# Backlight_V2.net
KiCad netlist of a schematic drawn in Altium Designer
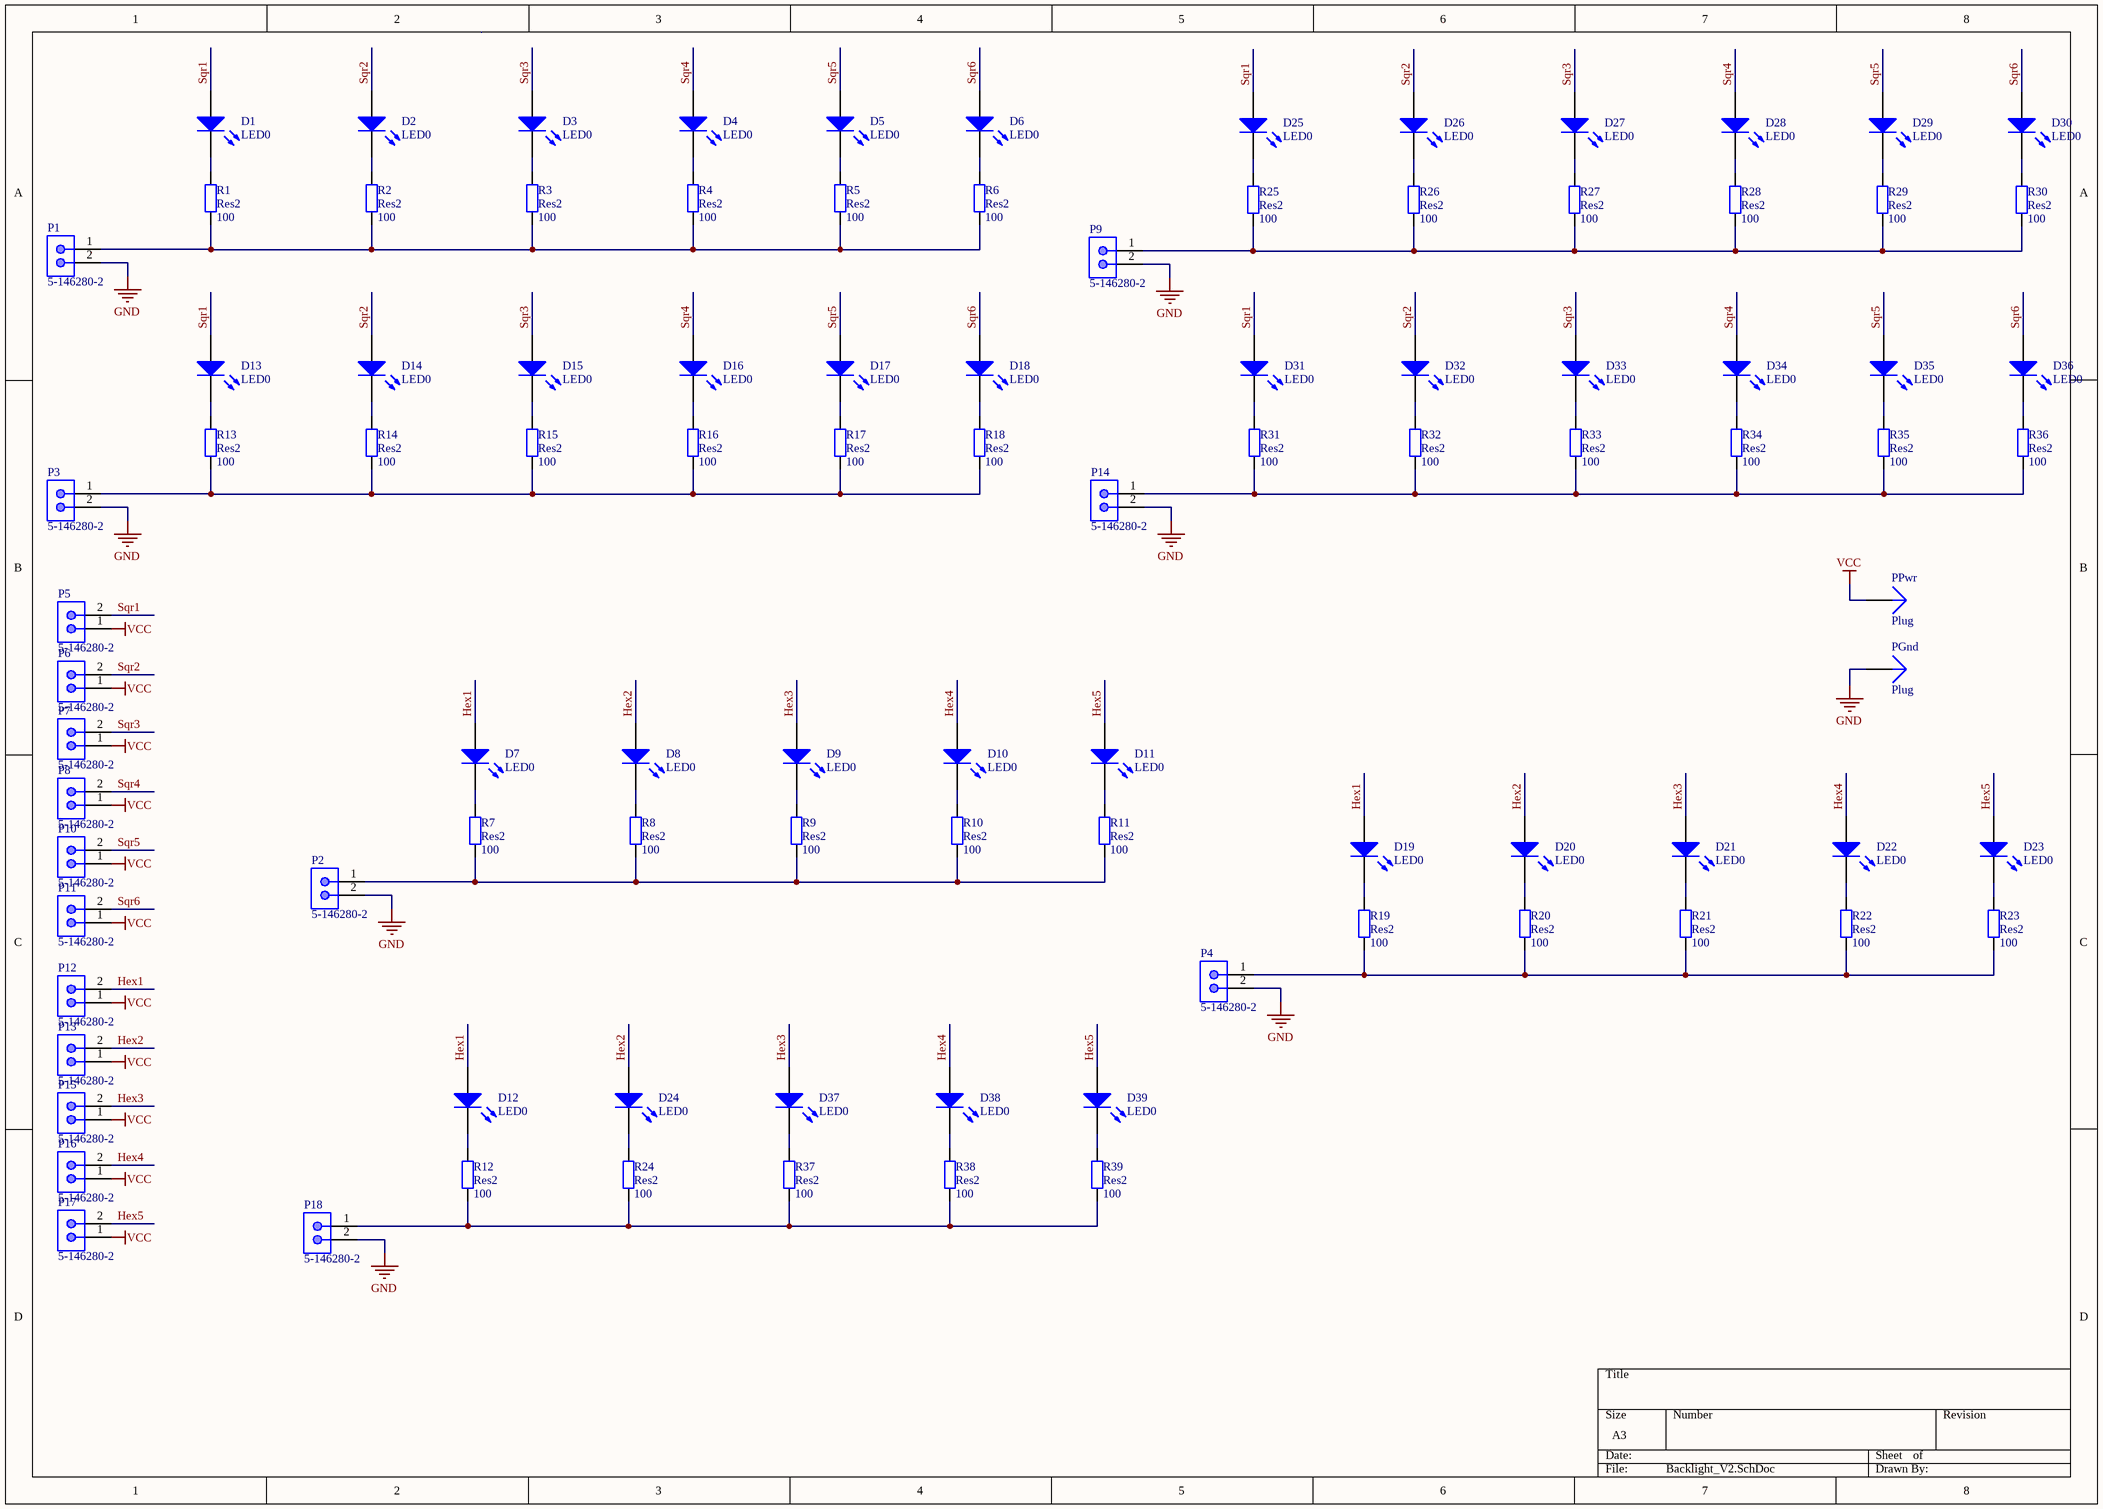
[diagram p0: Backlight_V2.SchDoc]

(export (version "E")
  (design (tool "Eeschema 10.0.6"))
  (components
    (comp (ref "D1")
      (value "LED0")
      (footprint "DIOM3528X07N")
      (description "Typical INFRARED GaAs LED")
      (fields (field (name "PUBLISHER") "Altium Limited"))
      (libsource (lib "Miscellaneous Devices") (part "LED0"))
    )
    (comp (ref "D2")
      (value "LED0")
      (footprint "DIOM3528X07N")
      (description "Typical INFRARED GaAs LED")
      (fields (field (name "PUBLISHER") "Altium Limited"))
      (libsource (lib "Miscellaneous Devices") (part "LED0"))
    )
    (comp (ref "D3")
      (value "LED0")
      (footprint "DIOM3528X07N")
      (description "Typical INFRARED GaAs LED")
      (fields (field (name "PUBLISHER") "Altium Limited"))
      (libsource (lib "Miscellaneous Devices") (part "LED0"))
    )
    (comp (ref "D4")
      (value "LED0")
      (footprint "DIOM3528X07N")
      (description "Typical INFRARED GaAs LED")
      (fields (field (name "PUBLISHER") "Altium Limited"))
      (libsource (lib "Miscellaneous Devices") (part "LED0"))
    )
    (comp (ref "D5")
      (value "LED0")
      (footprint "DIOM3528X07N")
      (description "Typical INFRARED GaAs LED")
      (fields (field (name "PUBLISHER") "Altium Limited"))
      (libsource (lib "Miscellaneous Devices") (part "LED0"))
    )
    (comp (ref "D6")
      (value "LED0")
      (footprint "DIOM3528X07N")
      (description "Typical INFRARED GaAs LED")
      (fields (field (name "PUBLISHER") "Altium Limited"))
      (libsource (lib "Miscellaneous Devices") (part "LED0"))
    )
    (comp (ref "D7")
      (value "LED0")
      (footprint "DIOM3528X07N")
      (description "Typical INFRARED GaAs LED")
      (fields (field (name "PUBLISHER") "Altium Limited"))
      (libsource (lib "Miscellaneous Devices") (part "LED0"))
    )
    (comp (ref "D8")
      (value "LED0")
      (footprint "DIOM3528X07N")
      (description "Typical INFRARED GaAs LED")
      (fields (field (name "PUBLISHER") "Altium Limited"))
      (libsource (lib "Miscellaneous Devices") (part "LED0"))
    )
    (comp (ref "D9")
      (value "LED0")
      (footprint "DIOM3528X07N")
      (description "Typical INFRARED GaAs LED")
      (fields (field (name "PUBLISHER") "Altium Limited"))
      (libsource (lib "Miscellaneous Devices") (part "LED0"))
    )
    (comp (ref "D10")
      (value "LED0")
      (footprint "DIOM3528X07N")
      (description "Typical INFRARED GaAs LED")
      (fields (field (name "PUBLISHER") "Altium Limited"))
      (libsource (lib "Miscellaneous Devices") (part "LED0"))
    )
    (comp (ref "D11")
      (value "LED0")
      (footprint "DIOM3528X07N")
      (description "Typical INFRARED GaAs LED")
      (fields (field (name "PUBLISHER") "Altium Limited"))
      (libsource (lib "Miscellaneous Devices") (part "LED0"))
    )
    (comp (ref "D12")
      (value "LED0")
      (footprint "DIOM3528X07N")
      (description "Typical INFRARED GaAs LED")
      (fields (field (name "PUBLISHER") "Altium Limited"))
      (libsource (lib "Miscellaneous Devices") (part "LED0"))
    )
    (comp (ref "D13")
      (value "LED0")
      (footprint "DIOM3528X07N")
      (description "Typical INFRARED GaAs LED")
      (fields (field (name "PUBLISHER") "Altium Limited"))
      (libsource (lib "Miscellaneous Devices") (part "LED0"))
    )
    (comp (ref "D14")
      (value "LED0")
      (footprint "DIOM3528X07N")
      (description "Typical INFRARED GaAs LED")
      (fields (field (name "PUBLISHER") "Altium Limited"))
      (libsource (lib "Miscellaneous Devices") (part "LED0"))
    )
    (comp (ref "D15")
      (value "LED0")
      (footprint "DIOM3528X07N")
      (description "Typical INFRARED GaAs LED")
      (fields (field (name "PUBLISHER") "Altium Limited"))
      (libsource (lib "Miscellaneous Devices") (part "LED0"))
    )
    (comp (ref "D16")
      (value "LED0")
      (footprint "DIOM3528X07N")
      (description "Typical INFRARED GaAs LED")
      (fields (field (name "PUBLISHER") "Altium Limited"))
      (libsource (lib "Miscellaneous Devices") (part "LED0"))
    )
    (comp (ref "D17")
      (value "LED0")
      (footprint "DIOM3528X07N")
      (description "Typical INFRARED GaAs LED")
      (fields (field (name "PUBLISHER") "Altium Limited"))
      (libsource (lib "Miscellaneous Devices") (part "LED0"))
    )
    (comp (ref "D18")
      (value "LED0")
      (footprint "DIOM3528X07N")
      (description "Typical INFRARED GaAs LED")
      (fields (field (name "PUBLISHER") "Altium Limited"))
      (libsource (lib "Miscellaneous Devices") (part "LED0"))
    )
    (comp (ref "D19")
      (value "LED0")
      (footprint "DIOM3528X07N")
      (description "Typical INFRARED GaAs LED")
      (fields (field (name "PUBLISHER") "Altium Limited"))
      (libsource (lib "Miscellaneous Devices") (part "LED0"))
    )
    (comp (ref "D20")
      (value "LED0")
      (footprint "DIOM3528X07N")
      (description "Typical INFRARED GaAs LED")
      (fields (field (name "PUBLISHER") "Altium Limited"))
      (libsource (lib "Miscellaneous Devices") (part "LED0"))
    )
    (comp (ref "D21")
      (value "LED0")
      (footprint "DIOM3528X07N")
      (description "Typical INFRARED GaAs LED")
      (fields (field (name "PUBLISHER") "Altium Limited"))
      (libsource (lib "Miscellaneous Devices") (part "LED0"))
    )
    (comp (ref "D22")
      (value "LED0")
      (footprint "DIOM3528X07N")
      (description "Typical INFRARED GaAs LED")
      (fields (field (name "PUBLISHER") "Altium Limited"))
      (libsource (lib "Miscellaneous Devices") (part "LED0"))
    )
    (comp (ref "D23")
      (value "LED0")
      (footprint "DIOM3528X07N")
      (description "Typical INFRARED GaAs LED")
      (fields (field (name "PUBLISHER") "Altium Limited"))
      (libsource (lib "Miscellaneous Devices") (part "LED0"))
    )
    (comp (ref "D24")
      (value "LED0")
      (footprint "DIOM3528X07N")
      (description "Typical INFRARED GaAs LED")
      (fields (field (name "PUBLISHER") "Altium Limited"))
      (libsource (lib "Miscellaneous Devices") (part "LED0"))
    )
    (comp (ref "D25")
      (value "LED0")
      (footprint "DIOM3528X07N")
      (description "Typical INFRARED GaAs LED")
      (fields (field (name "PUBLISHER") "Altium Limited"))
      (libsource (lib "Miscellaneous Devices") (part "LED0"))
    )
    (comp (ref "D26")
      (value "LED0")
      (footprint "DIOM3528X07N")
      (description "Typical INFRARED GaAs LED")
      (fields (field (name "PUBLISHER") "Altium Limited"))
      (libsource (lib "Miscellaneous Devices") (part "LED0"))
    )
    (comp (ref "D27")
      (value "LED0")
      (footprint "DIOM3528X07N")
      (description "Typical INFRARED GaAs LED")
      (fields (field (name "PUBLISHER") "Altium Limited"))
      (libsource (lib "Miscellaneous Devices") (part "LED0"))
    )
    (comp (ref "D28")
      (value "LED0")
      (footprint "DIOM3528X07N")
      (description "Typical INFRARED GaAs LED")
      (fields (field (name "PUBLISHER") "Altium Limited"))
      (libsource (lib "Miscellaneous Devices") (part "LED0"))
    )
    (comp (ref "D29")
      (value "LED0")
      (footprint "DIOM3528X07N")
      (description "Typical INFRARED GaAs LED")
      (fields (field (name "PUBLISHER") "Altium Limited"))
      (libsource (lib "Miscellaneous Devices") (part "LED0"))
    )
    (comp (ref "D30")
      (value "LED0")
      (footprint "DIOM3528X07N")
      (description "Typical INFRARED GaAs LED")
      (fields (field (name "PUBLISHER") "Altium Limited"))
      (libsource (lib "Miscellaneous Devices") (part "LED0"))
    )
    (comp (ref "D31")
      (value "LED0")
      (footprint "DIOM3528X07N")
      (description "Typical INFRARED GaAs LED")
      (fields (field (name "PUBLISHER") "Altium Limited"))
      (libsource (lib "Miscellaneous Devices") (part "LED0"))
    )
    (comp (ref "D32")
      (value "LED0")
      (footprint "DIOM3528X07N")
      (description "Typical INFRARED GaAs LED")
      (fields (field (name "PUBLISHER") "Altium Limited"))
      (libsource (lib "Miscellaneous Devices") (part "LED0"))
    )
    (comp (ref "D33")
      (value "LED0")
      (footprint "DIOM3528X07N")
      (description "Typical INFRARED GaAs LED")
      (fields (field (name "PUBLISHER") "Altium Limited"))
      (libsource (lib "Miscellaneous Devices") (part "LED0"))
    )
    (comp (ref "D34")
      (value "LED0")
      (footprint "DIOM3528X07N")
      (description "Typical INFRARED GaAs LED")
      (fields (field (name "PUBLISHER") "Altium Limited"))
      (libsource (lib "Miscellaneous Devices") (part "LED0"))
    )
    (comp (ref "D35")
      (value "LED0")
      (footprint "DIOM3528X07N")
      (description "Typical INFRARED GaAs LED")
      (fields (field (name "PUBLISHER") "Altium Limited"))
      (libsource (lib "Miscellaneous Devices") (part "LED0"))
    )
    (comp (ref "D36")
      (value "LED0")
      (footprint "DIOM3528X07N")
      (description "Typical INFRARED GaAs LED")
      (fields (field (name "PUBLISHER") "Altium Limited"))
      (libsource (lib "Miscellaneous Devices") (part "LED0"))
    )
    (comp (ref "D37")
      (value "LED0")
      (footprint "DIOM3528X07N")
      (description "Typical INFRARED GaAs LED")
      (fields (field (name "PUBLISHER") "Altium Limited"))
      (libsource (lib "Miscellaneous Devices") (part "LED0"))
    )
    (comp (ref "D38")
      (value "LED0")
      (footprint "DIOM3528X07N")
      (description "Typical INFRARED GaAs LED")
      (fields (field (name "PUBLISHER") "Altium Limited"))
      (libsource (lib "Miscellaneous Devices") (part "LED0"))
    )
    (comp (ref "D39")
      (value "LED0")
      (footprint "DIOM3528X07N")
      (description "Typical INFRARED GaAs LED")
      (fields (field (name "PUBLISHER") "Altium Limited"))
      (libsource (lib "Miscellaneous Devices") (part "LED0"))
    )
    (comp (ref "P1")
      (value "5-146280-2")
      (footprint "TECO-5-146280-2_V")
      (fields (field (name "MANUFACTURER") "TE Connectivity"))
      (libsource (lib "") (part "CN-1P-M-R2_1"))
    )
    (comp (ref "P2")
      (value "5-146280-2")
      (footprint "TECO-5-146280-2_V")
      (fields (field (name "MANUFACTURER") "TE Connectivity"))
      (libsource (lib "") (part "CN-1P-M-R2_1"))
    )
    (comp (ref "P3")
      (value "5-146280-2")
      (footprint "TECO-5-146280-2_V")
      (fields (field (name "MANUFACTURER") "TE Connectivity"))
      (libsource (lib "") (part "CN-1P-M-R2_1"))
    )
    (comp (ref "P4")
      (value "5-146280-2")
      (footprint "TECO-5-146280-2_V")
      (fields (field (name "MANUFACTURER") "TE Connectivity"))
      (libsource (lib "") (part "CN-1P-M-R2_1"))
    )
    (comp (ref "P5")
      (value "5-146280-2")
      (footprint "TECO-5-146280-2_V")
      (fields (field (name "MANUFACTURER") "TE Connectivity"))
      (libsource (lib "Altium Content Vault") (part "CN-1P-M-R2"))
    )
    (comp (ref "P6")
      (value "5-146280-2")
      (footprint "TECO-5-146280-2_V")
      (fields (field (name "MANUFACTURER") "TE Connectivity"))
      (libsource (lib "Altium Content Vault") (part "CN-1P-M-R2"))
    )
    (comp (ref "P7")
      (value "5-146280-2")
      (footprint "TECO-5-146280-2_V")
      (fields (field (name "MANUFACTURER") "TE Connectivity"))
      (libsource (lib "Altium Content Vault") (part "CN-1P-M-R2"))
    )
    (comp (ref "P8")
      (value "5-146280-2")
      (footprint "TECO-5-146280-2_V")
      (fields (field (name "MANUFACTURER") "TE Connectivity"))
      (libsource (lib "Altium Content Vault") (part "CN-1P-M-R2"))
    )
    (comp (ref "P9")
      (value "5-146280-2")
      (footprint "TECO-5-146280-2_V")
      (fields (field (name "MANUFACTURER") "TE Connectivity"))
      (libsource (lib "") (part "CN-1P-M-R2_1"))
    )
    (comp (ref "P10")
      (value "5-146280-2")
      (footprint "TECO-5-146280-2_V")
      (fields (field (name "MANUFACTURER") "TE Connectivity"))
      (libsource (lib "Altium Content Vault") (part "CN-1P-M-R2"))
    )
    (comp (ref "P11")
      (value "5-146280-2")
      (footprint "TECO-5-146280-2_V")
      (fields (field (name "MANUFACTURER") "TE Connectivity"))
      (libsource (lib "Altium Content Vault") (part "CN-1P-M-R2"))
    )
    (comp (ref "P12")
      (value "5-146280-2")
      (footprint "TECO-5-146280-2_V")
      (fields (field (name "MANUFACTURER") "TE Connectivity"))
      (libsource (lib "Altium Content Vault") (part "CN-1P-M-R2"))
    )
    (comp (ref "P13")
      (value "5-146280-2")
      (footprint "TECO-5-146280-2_V")
      (fields (field (name "MANUFACTURER") "TE Connectivity"))
      (libsource (lib "Altium Content Vault") (part "CN-1P-M-R2"))
    )
    (comp (ref "P14")
      (value "5-146280-2")
      (footprint "TECO-5-146280-2_V")
      (fields (field (name "MANUFACTURER") "TE Connectivity"))
      (libsource (lib "") (part "CN-1P-M-R2_1"))
    )
    (comp (ref "P15")
      (value "5-146280-2")
      (footprint "TECO-5-146280-2_V")
      (fields (field (name "MANUFACTURER") "TE Connectivity"))
      (libsource (lib "Altium Content Vault") (part "CN-1P-M-R2"))
    )
    (comp (ref "P16")
      (value "5-146280-2")
      (footprint "TECO-5-146280-2_V")
      (fields (field (name "MANUFACTURER") "TE Connectivity"))
      (libsource (lib "Altium Content Vault") (part "CN-1P-M-R2"))
    )
    (comp (ref "P17")
      (value "5-146280-2")
      (footprint "TECO-5-146280-2_V")
      (fields (field (name "MANUFACTURER") "TE Connectivity"))
      (libsource (lib "Altium Content Vault") (part "CN-1P-M-R2"))
    )
    (comp (ref "P18")
      (value "5-146280-2")
      (footprint "TECO-5-146280-2_V")
      (fields (field (name "MANUFACTURER") "TE Connectivity"))
      (libsource (lib "") (part "CN-1P-M-R2_1"))
    )
    (comp (ref "PGnd")
      (value "Plug")
      (footprint "Bananenbuchse")
      (fields (field (name "PUBLISHER") "Altium Limited"))
      (libsource (lib "Miscellaneous Connectors") (part "Plug"))
    )
    (comp (ref "PPwr")
      (value "Plug")
      (footprint "Bananenbuchse")
      (fields (field (name "PUBLISHER") "Altium Limited"))
      (libsource (lib "Miscellaneous Connectors") (part "Plug"))
    )
    (comp (ref "R1")
      (value "Res2")
      (footprint "6-0805_N")
      (description "Resistor")
      (fields (field (name "ALTIUM_VALUE") "100") (field (name "PUBLISHER") "Altium Limited"))
      (libsource (lib "Miscellaneous Devices") (part "Res2"))
    )
    (comp (ref "R2")
      (value "Res2")
      (footprint "6-0805_N")
      (description "Resistor")
      (fields (field (name "ALTIUM_VALUE") "100") (field (name "PUBLISHER") "Altium Limited"))
      (libsource (lib "Miscellaneous Devices") (part "Res2"))
    )
    (comp (ref "R3")
      (value "Res2")
      (footprint "6-0805_N")
      (description "Resistor")
      (fields (field (name "ALTIUM_VALUE") "100") (field (name "PUBLISHER") "Altium Limited"))
      (libsource (lib "Miscellaneous Devices") (part "Res2"))
    )
    (comp (ref "R4")
      (value "Res2")
      (footprint "6-0805_N")
      (description "Resistor")
      (fields (field (name "ALTIUM_VALUE") "100") (field (name "PUBLISHER") "Altium Limited"))
      (libsource (lib "Miscellaneous Devices") (part "Res2"))
    )
    (comp (ref "R5")
      (value "Res2")
      (footprint "6-0805_N")
      (description "Resistor")
      (fields (field (name "ALTIUM_VALUE") "100") (field (name "PUBLISHER") "Altium Limited"))
      (libsource (lib "Miscellaneous Devices") (part "Res2"))
    )
    (comp (ref "R6")
      (value "Res2")
      (footprint "6-0805_N")
      (description "Resistor")
      (fields (field (name "ALTIUM_VALUE") "100") (field (name "PUBLISHER") "Altium Limited"))
      (libsource (lib "Miscellaneous Devices") (part "Res2"))
    )
    (comp (ref "R7")
      (value "Res2")
      (footprint "6-0805_N")
      (description "Resistor")
      (fields (field (name "ALTIUM_VALUE") "100") (field (name "PUBLISHER") "Altium Limited"))
      (libsource (lib "Miscellaneous Devices") (part "Res2"))
    )
    (comp (ref "R8")
      (value "Res2")
      (footprint "6-0805_N")
      (description "Resistor")
      (fields (field (name "ALTIUM_VALUE") "100") (field (name "PUBLISHER") "Altium Limited"))
      (libsource (lib "Miscellaneous Devices") (part "Res2"))
    )
    (comp (ref "R9")
      (value "Res2")
      (footprint "6-0805_N")
      (description "Resistor")
      (fields (field (name "ALTIUM_VALUE") "100") (field (name "PUBLISHER") "Altium Limited"))
      (libsource (lib "Miscellaneous Devices") (part "Res2"))
    )
    (comp (ref "R10")
      (value "Res2")
      (footprint "6-0805_N")
      (description "Resistor")
      (fields (field (name "ALTIUM_VALUE") "100") (field (name "PUBLISHER") "Altium Limited"))
      (libsource (lib "Miscellaneous Devices") (part "Res2"))
    )
    (comp (ref "R11")
      (value "Res2")
      (footprint "6-0805_N")
      (description "Resistor")
      (fields (field (name "ALTIUM_VALUE") "100") (field (name "PUBLISHER") "Altium Limited"))
      (libsource (lib "Miscellaneous Devices") (part "Res2"))
    )
    (comp (ref "R12")
      (value "Res2")
      (footprint "6-0805_N")
      (description "Resistor")
      (fields (field (name "ALTIUM_VALUE") "100") (field (name "PUBLISHER") "Altium Limited"))
      (libsource (lib "Miscellaneous Devices") (part "Res2"))
    )
    (comp (ref "R13")
      (value "Res2")
      (footprint "6-0805_N")
      (description "Resistor")
      (fields (field (name "ALTIUM_VALUE") "100") (field (name "PUBLISHER") "Altium Limited"))
      (libsource (lib "Miscellaneous Devices") (part "Res2"))
    )
    (comp (ref "R14")
      (value "Res2")
      (footprint "6-0805_N")
      (description "Resistor")
      (fields (field (name "ALTIUM_VALUE") "100") (field (name "PUBLISHER") "Altium Limited"))
      (libsource (lib "Miscellaneous Devices") (part "Res2"))
    )
    (comp (ref "R15")
      (value "Res2")
      (footprint "6-0805_N")
      (description "Resistor")
      (fields (field (name "ALTIUM_VALUE") "100") (field (name "PUBLISHER") "Altium Limited"))
      (libsource (lib "Miscellaneous Devices") (part "Res2"))
    )
    (comp (ref "R16")
      (value "Res2")
      (footprint "6-0805_N")
      (description "Resistor")
      (fields (field (name "ALTIUM_VALUE") "100") (field (name "PUBLISHER") "Altium Limited"))
      (libsource (lib "Miscellaneous Devices") (part "Res2"))
    )
    (comp (ref "R17")
      (value "Res2")
      (footprint "6-0805_N")
      (description "Resistor")
      (fields (field (name "ALTIUM_VALUE") "100") (field (name "PUBLISHER") "Altium Limited"))
      (libsource (lib "Miscellaneous Devices") (part "Res2"))
    )
    (comp (ref "R18")
      (value "Res2")
      (footprint "6-0805_N")
      (description "Resistor")
      (fields (field (name "ALTIUM_VALUE") "100") (field (name "PUBLISHER") "Altium Limited"))
      (libsource (lib "Miscellaneous Devices") (part "Res2"))
    )
    (comp (ref "R19")
      (value "Res2")
      (footprint "6-0805_N")
      (description "Resistor")
      (fields (field (name "ALTIUM_VALUE") "100") (field (name "PUBLISHER") "Altium Limited"))
      (libsource (lib "Miscellaneous Devices") (part "Res2"))
    )
    (comp (ref "R20")
      (value "Res2")
      (footprint "6-0805_N")
      (description "Resistor")
      (fields (field (name "ALTIUM_VALUE") "100") (field (name "PUBLISHER") "Altium Limited"))
      (libsource (lib "Miscellaneous Devices") (part "Res2"))
    )
    (comp (ref "R21")
      (value "Res2")
      (footprint "6-0805_N")
      (description "Resistor")
      (fields (field (name "ALTIUM_VALUE") "100") (field (name "PUBLISHER") "Altium Limited"))
      (libsource (lib "Miscellaneous Devices") (part "Res2"))
    )
    (comp (ref "R22")
      (value "Res2")
      (footprint "6-0805_N")
      (description "Resistor")
      (fields (field (name "ALTIUM_VALUE") "100") (field (name "PUBLISHER") "Altium Limited"))
      (libsource (lib "Miscellaneous Devices") (part "Res2"))
    )
    (comp (ref "R23")
      (value "Res2")
      (footprint "6-0805_N")
      (description "Resistor")
      (fields (field (name "ALTIUM_VALUE") "100") (field (name "PUBLISHER") "Altium Limited"))
      (libsource (lib "Miscellaneous Devices") (part "Res2"))
    )
    (comp (ref "R24")
      (value "Res2")
      (footprint "6-0805_N")
      (description "Resistor")
      (fields (field (name "ALTIUM_VALUE") "100") (field (name "PUBLISHER") "Altium Limited"))
      (libsource (lib "Miscellaneous Devices") (part "Res2"))
    )
    (comp (ref "R25")
      (value "Res2")
      (footprint "6-0805_N")
      (description "Resistor")
      (fields (field (name "ALTIUM_VALUE") "100") (field (name "PUBLISHER") "Altium Limited"))
      (libsource (lib "Miscellaneous Devices") (part "Res2"))
    )
    (comp (ref "R26")
      (value "Res2")
      (footprint "6-0805_N")
      (description "Resistor")
      (fields (field (name "ALTIUM_VALUE") "100") (field (name "PUBLISHER") "Altium Limited"))
      (libsource (lib "Miscellaneous Devices") (part "Res2"))
    )
    (comp (ref "R27")
      (value "Res2")
      (footprint "6-0805_N")
      (description "Resistor")
      (fields (field (name "ALTIUM_VALUE") "100") (field (name "PUBLISHER") "Altium Limited"))
      (libsource (lib "Miscellaneous Devices") (part "Res2"))
    )
    (comp (ref "R28")
      (value "Res2")
      (footprint "6-0805_N")
      (description "Resistor")
      (fields (field (name "ALTIUM_VALUE") "100") (field (name "PUBLISHER") "Altium Limited"))
      (libsource (lib "Miscellaneous Devices") (part "Res2"))
    )
    (comp (ref "R29")
      (value "Res2")
      (footprint "6-0805_N")
      (description "Resistor")
      (fields (field (name "ALTIUM_VALUE") "100") (field (name "PUBLISHER") "Altium Limited"))
      (libsource (lib "Miscellaneous Devices") (part "Res2"))
    )
    (comp (ref "R30")
      (value "Res2")
      (footprint "6-0805_N")
      (description "Resistor")
      (fields (field (name "ALTIUM_VALUE") "100") (field (name "PUBLISHER") "Altium Limited"))
      (libsource (lib "Miscellaneous Devices") (part "Res2"))
    )
    (comp (ref "R31")
      (value "Res2")
      (footprint "6-0805_N")
      (description "Resistor")
      (fields (field (name "ALTIUM_VALUE") "100") (field (name "PUBLISHER") "Altium Limited"))
      (libsource (lib "Miscellaneous Devices") (part "Res2"))
    )
    (comp (ref "R32")
      (value "Res2")
      (footprint "6-0805_N")
      (description "Resistor")
      (fields (field (name "ALTIUM_VALUE") "100") (field (name "PUBLISHER") "Altium Limited"))
      (libsource (lib "Miscellaneous Devices") (part "Res2"))
    )
    (comp (ref "R33")
      (value "Res2")
      (footprint "6-0805_N")
      (description "Resistor")
      (fields (field (name "ALTIUM_VALUE") "100") (field (name "PUBLISHER") "Altium Limited"))
      (libsource (lib "Miscellaneous Devices") (part "Res2"))
    )
    (comp (ref "R34")
      (value "Res2")
      (footprint "6-0805_N")
      (description "Resistor")
      (fields (field (name "ALTIUM_VALUE") "100") (field (name "PUBLISHER") "Altium Limited"))
      (libsource (lib "Miscellaneous Devices") (part "Res2"))
    )
    (comp (ref "R35")
      (value "Res2")
      (footprint "6-0805_N")
      (description "Resistor")
      (fields (field (name "ALTIUM_VALUE") "100") (field (name "PUBLISHER") "Altium Limited"))
      (libsource (lib "Miscellaneous Devices") (part "Res2"))
    )
    (comp (ref "R36")
      (value "Res2")
      (footprint "6-0805_N")
      (description "Resistor")
      (fields (field (name "ALTIUM_VALUE") "100") (field (name "PUBLISHER") "Altium Limited"))
      (libsource (lib "Miscellaneous Devices") (part "Res2"))
    )
    (comp (ref "R37")
      (value "Res2")
      (footprint "6-0805_N")
      (description "Resistor")
      (fields (field (name "ALTIUM_VALUE") "100") (field (name "PUBLISHER") "Altium Limited"))
      (libsource (lib "Miscellaneous Devices") (part "Res2"))
    )
    (comp (ref "R38")
      (value "Res2")
      (footprint "6-0805_N")
      (description "Resistor")
      (fields (field (name "ALTIUM_VALUE") "100") (field (name "PUBLISHER") "Altium Limited"))
      (libsource (lib "Miscellaneous Devices") (part "Res2"))
    )
    (comp (ref "R39")
      (value "Res2")
      (footprint "6-0805_N")
      (description "Resistor")
      (fields (field (name "ALTIUM_VALUE") "100") (field (name "PUBLISHER") "Altium Limited"))
      (libsource (lib "Miscellaneous Devices") (part "Res2"))
    )
  )
  (nets
    (net (code "1") (name "/Hex1") (class "Default")
      (node (ref "D12") (pin "1") (pinfunction "A_1") (pintype "passive"))
      (node (ref "D19") (pin "1") (pinfunction "A_1") (pintype "passive"))
      (node (ref "D7") (pin "1") (pinfunction "A_1") (pintype "passive"))
      (node (ref "P12") (pin "2") (pinfunction "2_2") (pintype "passive"))
    )
    (net (code "2") (name "/Hex2") (class "Default")
      (node (ref "D20") (pin "1") (pinfunction "A_1") (pintype "passive"))
      (node (ref "D24") (pin "1") (pinfunction "A_1") (pintype "passive"))
      (node (ref "D8") (pin "1") (pinfunction "A_1") (pintype "passive"))
      (node (ref "P13") (pin "2") (pinfunction "2_2") (pintype "passive"))
    )
    (net (code "3") (name "/Hex3") (class "Default")
      (node (ref "D21") (pin "1") (pinfunction "A_1") (pintype "passive"))
      (node (ref "D37") (pin "1") (pinfunction "A_1") (pintype "passive"))
      (node (ref "D9") (pin "1") (pinfunction "A_1") (pintype "passive"))
      (node (ref "P15") (pin "2") (pinfunction "2_2") (pintype "passive"))
    )
    (net (code "4") (name "/Hex4") (class "Default")
      (node (ref "D10") (pin "1") (pinfunction "A_1") (pintype "passive"))
      (node (ref "D22") (pin "1") (pinfunction "A_1") (pintype "passive"))
      (node (ref "D38") (pin "1") (pinfunction "A_1") (pintype "passive"))
      (node (ref "P16") (pin "2") (pinfunction "2_2") (pintype "passive"))
    )
    (net (code "5") (name "/Hex5") (class "Default")
      (node (ref "D11") (pin "1") (pinfunction "A_1") (pintype "passive"))
      (node (ref "D23") (pin "1") (pinfunction "A_1") (pintype "passive"))
      (node (ref "D39") (pin "1") (pinfunction "A_1") (pintype "passive"))
      (node (ref "P17") (pin "2") (pinfunction "2_2") (pintype "passive"))
    )
    (net (code "6") (name "/Sqr1") (class "Default")
      (node (ref "D1") (pin "1") (pinfunction "A_1") (pintype "passive"))
      (node (ref "D13") (pin "1") (pinfunction "A_1") (pintype "passive"))
      (node (ref "D25") (pin "1") (pinfunction "A_1") (pintype "passive"))
      (node (ref "D31") (pin "1") (pinfunction "A_1") (pintype "passive"))
      (node (ref "P5") (pin "2") (pinfunction "2_2") (pintype "passive"))
    )
    (net (code "7") (name "/Sqr2") (class "Default")
      (node (ref "D14") (pin "1") (pinfunction "A_1") (pintype "passive"))
      (node (ref "D2") (pin "1") (pinfunction "A_1") (pintype "passive"))
      (node (ref "D26") (pin "1") (pinfunction "A_1") (pintype "passive"))
      (node (ref "D32") (pin "1") (pinfunction "A_1") (pintype "passive"))
      (node (ref "P6") (pin "2") (pinfunction "2_2") (pintype "passive"))
    )
    (net (code "8") (name "/Sqr3") (class "Default")
      (node (ref "D15") (pin "1") (pinfunction "A_1") (pintype "passive"))
      (node (ref "D27") (pin "1") (pinfunction "A_1") (pintype "passive"))
      (node (ref "D3") (pin "1") (pinfunction "A_1") (pintype "passive"))
      (node (ref "D33") (pin "1") (pinfunction "A_1") (pintype "passive"))
      (node (ref "P7") (pin "2") (pinfunction "2_2") (pintype "passive"))
    )
    (net (code "9") (name "/Sqr4") (class "Default")
      (node (ref "D16") (pin "1") (pinfunction "A_1") (pintype "passive"))
      (node (ref "D28") (pin "1") (pinfunction "A_1") (pintype "passive"))
      (node (ref "D34") (pin "1") (pinfunction "A_1") (pintype "passive"))
      (node (ref "D4") (pin "1") (pinfunction "A_1") (pintype "passive"))
      (node (ref "P8") (pin "2") (pinfunction "2_2") (pintype "passive"))
    )
    (net (code "10") (name "/Sqr5") (class "Default")
      (node (ref "D17") (pin "1") (pinfunction "A_1") (pintype "passive"))
      (node (ref "D29") (pin "1") (pinfunction "A_1") (pintype "passive"))
      (node (ref "D35") (pin "1") (pinfunction "A_1") (pintype "passive"))
      (node (ref "D5") (pin "1") (pinfunction "A_1") (pintype "passive"))
      (node (ref "P10") (pin "2") (pinfunction "2_2") (pintype "passive"))
    )
    (net (code "11") (name "/Sqr6") (class "Default")
      (node (ref "D18") (pin "1") (pinfunction "A_1") (pintype "passive"))
      (node (ref "D30") (pin "1") (pinfunction "A_1") (pintype "passive"))
      (node (ref "D36") (pin "1") (pinfunction "A_1") (pintype "passive"))
      (node (ref "D6") (pin "1") (pinfunction "A_1") (pintype "passive"))
      (node (ref "P11") (pin "2") (pinfunction "2_2") (pintype "passive"))
    )
    (net (code "12") (name "GND") (class "Default")
      (node (ref "P1") (pin "2") (pinfunction "2_2") (pintype "passive"))
      (node (ref "P14") (pin "2") (pinfunction "2_2") (pintype "passive"))
      (node (ref "P18") (pin "2") (pinfunction "2_2") (pintype "passive"))
      (node (ref "P2") (pin "2") (pinfunction "2_2") (pintype "passive"))
      (node (ref "P3") (pin "2") (pinfunction "2_2") (pintype "passive"))
      (node (ref "P4") (pin "2") (pinfunction "2_2") (pintype "passive"))
      (node (ref "P9") (pin "2") (pinfunction "2_2") (pintype "passive"))
      (node (ref "PGnd") (pin "1") (pinfunction "1_1") (pintype "passive"))
    )
    (net (code "13") (name "Net-(D1-K)") (class "Default")
      (node (ref "D1") (pin "2") (pinfunction "K_2") (pintype "passive"))
      (node (ref "R1") (pin "2") (pinfunction "2_2") (pintype "passive"))
    )
    (net (code "14") (name "Net-(D2-K)") (class "Default")
      (node (ref "D2") (pin "2") (pinfunction "K_2") (pintype "passive"))
      (node (ref "R2") (pin "2") (pinfunction "2_2") (pintype "passive"))
    )
    (net (code "15") (name "Net-(D3-K)") (class "Default")
      (node (ref "D3") (pin "2") (pinfunction "K_2") (pintype "passive"))
      (node (ref "R3") (pin "2") (pinfunction "2_2") (pintype "passive"))
    )
    (net (code "16") (name "Net-(D4-K)") (class "Default")
      (node (ref "D4") (pin "2") (pinfunction "K_2") (pintype "passive"))
      (node (ref "R4") (pin "2") (pinfunction "2_2") (pintype "passive"))
    )
    (net (code "17") (name "Net-(D5-K)") (class "Default")
      (node (ref "D5") (pin "2") (pinfunction "K_2") (pintype "passive"))
      (node (ref "R5") (pin "2") (pinfunction "2_2") (pintype "passive"))
    )
    (net (code "18") (name "Net-(D6-K)") (class "Default")
      (node (ref "D6") (pin "2") (pinfunction "K_2") (pintype "passive"))
      (node (ref "R6") (pin "2") (pinfunction "2_2") (pintype "passive"))
    )
    (net (code "19") (name "Net-(D7-K)") (class "Default")
      (node (ref "D7") (pin "2") (pinfunction "K_2") (pintype "passive"))
      (node (ref "R7") (pin "2") (pinfunction "2_2") (pintype "passive"))
    )
    (net (code "20") (name "Net-(D8-K)") (class "Default")
      (node (ref "D8") (pin "2") (pinfunction "K_2") (pintype "passive"))
      (node (ref "R8") (pin "2") (pinfunction "2_2") (pintype "passive"))
    )
    (net (code "21") (name "Net-(D9-K)") (class "Default")
      (node (ref "D9") (pin "2") (pinfunction "K_2") (pintype "passive"))
      (node (ref "R9") (pin "2") (pinfunction "2_2") (pintype "passive"))
    )
    (net (code "22") (name "Net-(D10-K)") (class "Default")
      (node (ref "D10") (pin "2") (pinfunction "K_2") (pintype "passive"))
      (node (ref "R10") (pin "2") (pinfunction "2_2") (pintype "passive"))
    )
    (net (code "23") (name "Net-(D11-K)") (class "Default")
      (node (ref "D11") (pin "2") (pinfunction "K_2") (pintype "passive"))
      (node (ref "R11") (pin "2") (pinfunction "2_2") (pintype "passive"))
    )
    (net (code "24") (name "Net-(D12-K)") (class "Default")
      (node (ref "D12") (pin "2") (pinfunction "K_2") (pintype "passive"))
      (node (ref "R12") (pin "2") (pinfunction "2_2") (pintype "passive"))
    )
    (net (code "25") (name "Net-(D13-K)") (class "Default")
      (node (ref "D13") (pin "2") (pinfunction "K_2") (pintype "passive"))
      (node (ref "R13") (pin "2") (pinfunction "2_2") (pintype "passive"))
    )
    (net (code "26") (name "Net-(D14-K)") (class "Default")
      (node (ref "D14") (pin "2") (pinfunction "K_2") (pintype "passive"))
      (node (ref "R14") (pin "2") (pinfunction "2_2") (pintype "passive"))
    )
    (net (code "27") (name "Net-(D15-K)") (class "Default")
      (node (ref "D15") (pin "2") (pinfunction "K_2") (pintype "passive"))
      (node (ref "R15") (pin "2") (pinfunction "2_2") (pintype "passive"))
    )
    (net (code "28") (name "Net-(D16-K)") (class "Default")
      (node (ref "D16") (pin "2") (pinfunction "K_2") (pintype "passive"))
      (node (ref "R16") (pin "2") (pinfunction "2_2") (pintype "passive"))
    )
    (net (code "29") (name "Net-(D17-K)") (class "Default")
      (node (ref "D17") (pin "2") (pinfunction "K_2") (pintype "passive"))
      (node (ref "R17") (pin "2") (pinfunction "2_2") (pintype "passive"))
    )
    (net (code "30") (name "Net-(D18-K)") (class "Default")
      (node (ref "D18") (pin "2") (pinfunction "K_2") (pintype "passive"))
      (node (ref "R18") (pin "2") (pinfunction "2_2") (pintype "passive"))
    )
    (net (code "31") (name "Net-(D19-K)") (class "Default")
      (node (ref "D19") (pin "2") (pinfunction "K_2") (pintype "passive"))
      (node (ref "R19") (pin "2") (pinfunction "2_2") (pintype "passive"))
    )
    (net (code "32") (name "Net-(D20-K)") (class "Default")
      (node (ref "D20") (pin "2") (pinfunction "K_2") (pintype "passive"))
      (node (ref "R20") (pin "2") (pinfunction "2_2") (pintype "passive"))
    )
    (net (code "33") (name "Net-(D21-K)") (class "Default")
      (node (ref "D21") (pin "2") (pinfunction "K_2") (pintype "passive"))
      (node (ref "R21") (pin "2") (pinfunction "2_2") (pintype "passive"))
    )
    (net (code "34") (name "Net-(D22-K)") (class "Default")
      (node (ref "D22") (pin "2") (pinfunction "K_2") (pintype "passive"))
      (node (ref "R22") (pin "2") (pinfunction "2_2") (pintype "passive"))
    )
    (net (code "35") (name "Net-(D23-K)") (class "Default")
      (node (ref "D23") (pin "2") (pinfunction "K_2") (pintype "passive"))
      (node (ref "R23") (pin "2") (pinfunction "2_2") (pintype "passive"))
    )
    (net (code "36") (name "Net-(D24-K)") (class "Default")
      (node (ref "D24") (pin "2") (pinfunction "K_2") (pintype "passive"))
      (node (ref "R24") (pin "2") (pinfunction "2_2") (pintype "passive"))
    )
    (net (code "37") (name "Net-(D25-K)") (class "Default")
      (node (ref "D25") (pin "2") (pinfunction "K_2") (pintype "passive"))
      (node (ref "R25") (pin "2") (pinfunction "2_2") (pintype "passive"))
    )
    (net (code "38") (name "Net-(D26-K)") (class "Default")
      (node (ref "D26") (pin "2") (pinfunction "K_2") (pintype "passive"))
      (node (ref "R26") (pin "2") (pinfunction "2_2") (pintype "passive"))
    )
    (net (code "39") (name "Net-(D27-K)") (class "Default")
      (node (ref "D27") (pin "2") (pinfunction "K_2") (pintype "passive"))
      (node (ref "R27") (pin "2") (pinfunction "2_2") (pintype "passive"))
    )
    (net (code "40") (name "Net-(D28-K)") (class "Default")
      (node (ref "D28") (pin "2") (pinfunction "K_2") (pintype "passive"))
      (node (ref "R28") (pin "2") (pinfunction "2_2") (pintype "passive"))
    )
    (net (code "41") (name "Net-(D29-K)") (class "Default")
      (node (ref "D29") (pin "2") (pinfunction "K_2") (pintype "passive"))
      (node (ref "R29") (pin "2") (pinfunction "2_2") (pintype "passive"))
    )
    (net (code "42") (name "Net-(D30-K)") (class "Default")
      (node (ref "D30") (pin "2") (pinfunction "K_2") (pintype "passive"))
      (node (ref "R30") (pin "2") (pinfunction "2_2") (pintype "passive"))
    )
    (net (code "43") (name "Net-(D31-K)") (class "Default")
      (node (ref "D31") (pin "2") (pinfunction "K_2") (pintype "passive"))
      (node (ref "R31") (pin "2") (pinfunction "2_2") (pintype "passive"))
    )
    (net (code "44") (name "Net-(D32-K)") (class "Default")
      (node (ref "D32") (pin "2") (pinfunction "K_2") (pintype "passive"))
      (node (ref "R32") (pin "2") (pinfunction "2_2") (pintype "passive"))
    )
    (net (code "45") (name "Net-(D33-K)") (class "Default")
      (node (ref "D33") (pin "2") (pinfunction "K_2") (pintype "passive"))
      (node (ref "R33") (pin "2") (pinfunction "2_2") (pintype "passive"))
    )
    (net (code "46") (name "Net-(D34-K)") (class "Default")
      (node (ref "D34") (pin "2") (pinfunction "K_2") (pintype "passive"))
      (node (ref "R34") (pin "2") (pinfunction "2_2") (pintype "passive"))
    )
    (net (code "47") (name "Net-(D35-K)") (class "Default")
      (node (ref "D35") (pin "2") (pinfunction "K_2") (pintype "passive"))
      (node (ref "R35") (pin "2") (pinfunction "2_2") (pintype "passive"))
    )
    (net (code "48") (name "Net-(D36-K)") (class "Default")
      (node (ref "D36") (pin "2") (pinfunction "K_2") (pintype "passive"))
      (node (ref "R36") (pin "2") (pinfunction "2_2") (pintype "passive"))
    )
    (net (code "49") (name "Net-(D37-K)") (class "Default")
      (node (ref "D37") (pin "2") (pinfunction "K_2") (pintype "passive"))
      (node (ref "R37") (pin "2") (pinfunction "2_2") (pintype "passive"))
    )
    (net (code "50") (name "Net-(D38-K)") (class "Default")
      (node (ref "D38") (pin "2") (pinfunction "K_2") (pintype "passive"))
      (node (ref "R38") (pin "2") (pinfunction "2_2") (pintype "passive"))
    )
    (net (code "51") (name "Net-(D39-K)") (class "Default")
      (node (ref "D39") (pin "2") (pinfunction "K_2") (pintype "passive"))
      (node (ref "R39") (pin "2") (pinfunction "2_2") (pintype "passive"))
    )
    (net (code "52") (name "Net-(P1-Pad1)") (class "Default")
      (node (ref "P1") (pin "1") (pinfunction "1_1") (pintype "passive"))
      (node (ref "R1") (pin "1") (pinfunction "1_1") (pintype "passive"))
      (node (ref "R2") (pin "1") (pinfunction "1_1") (pintype "passive"))
      (node (ref "R3") (pin "1") (pinfunction "1_1") (pintype "passive"))
      (node (ref "R4") (pin "1") (pinfunction "1_1") (pintype "passive"))
      (node (ref "R5") (pin "1") (pinfunction "1_1") (pintype "passive"))
      (node (ref "R6") (pin "1") (pinfunction "1_1") (pintype "passive"))
    )
    (net (code "53") (name "Net-(P2-Pad1)") (class "Default")
      (node (ref "P2") (pin "1") (pinfunction "1_1") (pintype "passive"))
      (node (ref "R10") (pin "1") (pinfunction "1_1") (pintype "passive"))
      (node (ref "R11") (pin "1") (pinfunction "1_1") (pintype "passive"))
      (node (ref "R7") (pin "1") (pinfunction "1_1") (pintype "passive"))
      (node (ref "R8") (pin "1") (pinfunction "1_1") (pintype "passive"))
      (node (ref "R9") (pin "1") (pinfunction "1_1") (pintype "passive"))
    )
    (net (code "54") (name "Net-(P3-Pad1)") (class "Default")
      (node (ref "P3") (pin "1") (pinfunction "1_1") (pintype "passive"))
      (node (ref "R13") (pin "1") (pinfunction "1_1") (pintype "passive"))
      (node (ref "R14") (pin "1") (pinfunction "1_1") (pintype "passive"))
      (node (ref "R15") (pin "1") (pinfunction "1_1") (pintype "passive"))
      (node (ref "R16") (pin "1") (pinfunction "1_1") (pintype "passive"))
      (node (ref "R17") (pin "1") (pinfunction "1_1") (pintype "passive"))
      (node (ref "R18") (pin "1") (pinfunction "1_1") (pintype "passive"))
    )
    (net (code "55") (name "Net-(P4-Pad1)") (class "Default")
      (node (ref "P4") (pin "1") (pinfunction "1_1") (pintype "passive"))
      (node (ref "R19") (pin "1") (pinfunction "1_1") (pintype "passive"))
      (node (ref "R20") (pin "1") (pinfunction "1_1") (pintype "passive"))
      (node (ref "R21") (pin "1") (pinfunction "1_1") (pintype "passive"))
      (node (ref "R22") (pin "1") (pinfunction "1_1") (pintype "passive"))
      (node (ref "R23") (pin "1") (pinfunction "1_1") (pintype "passive"))
    )
    (net (code "56") (name "Net-(P9-Pad1)") (class "Default")
      (node (ref "P9") (pin "1") (pinfunction "1_1") (pintype "passive"))
      (node (ref "R25") (pin "1") (pinfunction "1_1") (pintype "passive"))
      (node (ref "R26") (pin "1") (pinfunction "1_1") (pintype "passive"))
      (node (ref "R27") (pin "1") (pinfunction "1_1") (pintype "passive"))
      (node (ref "R28") (pin "1") (pinfunction "1_1") (pintype "passive"))
      (node (ref "R29") (pin "1") (pinfunction "1_1") (pintype "passive"))
      (node (ref "R30") (pin "1") (pinfunction "1_1") (pintype "passive"))
    )
    (net (code "57") (name "Net-(P14-Pad1)") (class "Default")
      (node (ref "P14") (pin "1") (pinfunction "1_1") (pintype "passive"))
      (node (ref "R31") (pin "1") (pinfunction "1_1") (pintype "passive"))
      (node (ref "R32") (pin "1") (pinfunction "1_1") (pintype "passive"))
      (node (ref "R33") (pin "1") (pinfunction "1_1") (pintype "passive"))
      (node (ref "R34") (pin "1") (pinfunction "1_1") (pintype "passive"))
      (node (ref "R35") (pin "1") (pinfunction "1_1") (pintype "passive"))
      (node (ref "R36") (pin "1") (pinfunction "1_1") (pintype "passive"))
    )
    (net (code "58") (name "Net-(P18-Pad1)") (class "Default")
      (node (ref "P18") (pin "1") (pinfunction "1_1") (pintype "passive"))
      (node (ref "R12") (pin "1") (pinfunction "1_1") (pintype "passive"))
      (node (ref "R24") (pin "1") (pinfunction "1_1") (pintype "passive"))
      (node (ref "R37") (pin "1") (pinfunction "1_1") (pintype "passive"))
      (node (ref "R38") (pin "1") (pinfunction "1_1") (pintype "passive"))
      (node (ref "R39") (pin "1") (pinfunction "1_1") (pintype "passive"))
    )
    (net (code "59") (name "VCC") (class "Default")
      (node (ref "P10") (pin "1") (pinfunction "1_1") (pintype "passive"))
      (node (ref "P11") (pin "1") (pinfunction "1_1") (pintype "passive"))
      (node (ref "P12") (pin "1") (pinfunction "1_1") (pintype "passive"))
      (node (ref "P13") (pin "1") (pinfunction "1_1") (pintype "passive"))
      (node (ref "P15") (pin "1") (pinfunction "1_1") (pintype "passive"))
      (node (ref "P16") (pin "1") (pinfunction "1_1") (pintype "passive"))
      (node (ref "P17") (pin "1") (pinfunction "1_1") (pintype "passive"))
      (node (ref "P5") (pin "1") (pinfunction "1_1") (pintype "passive"))
      (node (ref "P6") (pin "1") (pinfunction "1_1") (pintype "passive"))
      (node (ref "P7") (pin "1") (pinfunction "1_1") (pintype "passive"))
      (node (ref "P8") (pin "1") (pinfunction "1_1") (pintype "passive"))
      (node (ref "PPwr") (pin "1") (pinfunction "1_1") (pintype "passive"))
    )
  )
)
